# MCU.net
KiCad netlist of a schematic drawn in Altium Designer
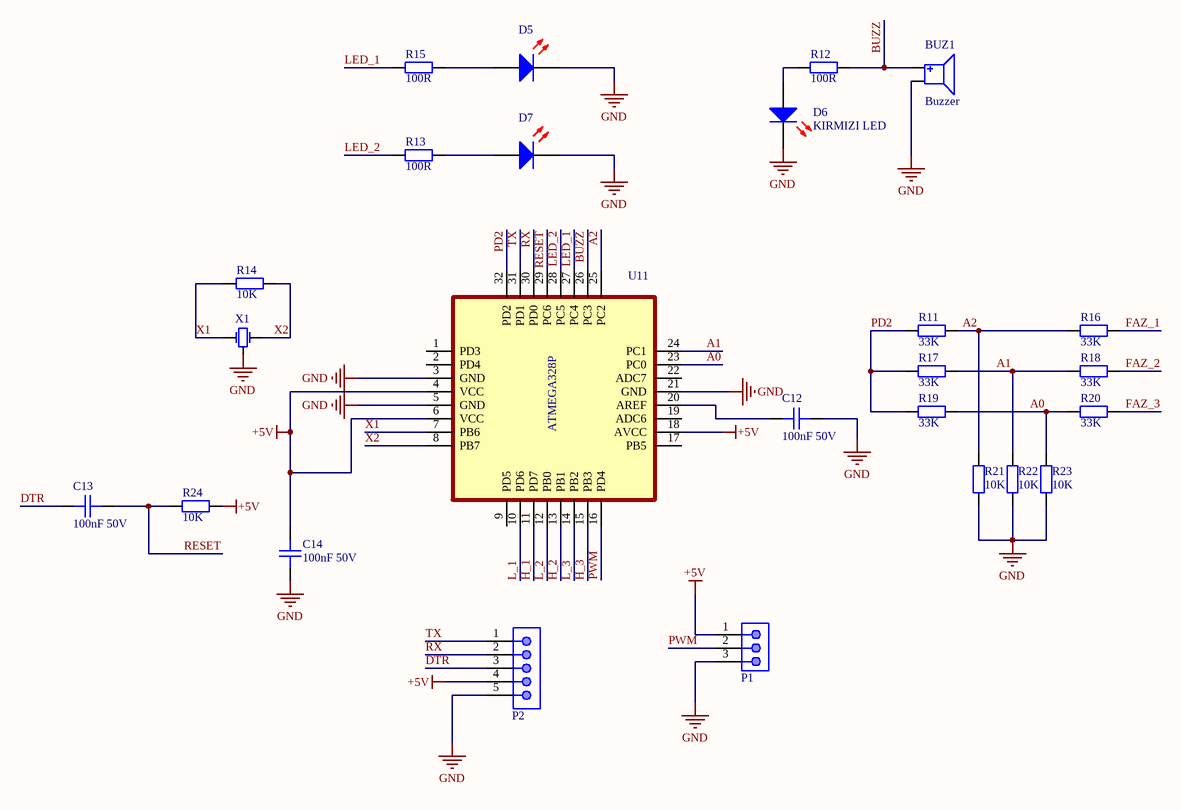
[diagram p0: MCU.SchDoc]

(export (version "E")
  (design (tool "Eeschema 10.0.6"))
  (components
    (comp (ref "BUZ1")
      (value "BUZZER MAGN 3.6V 7.5X7.5MM SMD")
      (footprint "BUZ: CMT-7525")
      (fields (field (name "DEGER") "Buzzer"))
      (libsource (lib "PROJE") (part "Buzzer(CMT-7525-80-SMT-TR)"))
    )
    (comp (ref "C12")
      (value "CAP CER 0.1UF 50V X7R 0805")
      (footprint "CAP 0805/2012")
      (description "0.1µF ±10% 50V Ceramic Capacitor X7R 0805 (2012 Metric)")
      (fields (field (name "DEGER") "100nF 50V"))
      (libsource (lib "PROJE") (part "100nF 50V 0805"))
    )
    (comp (ref "C13")
      (value "CAP CER 0.1UF 50V X7R 0805")
      (footprint "CAP 0805/2012")
      (description "0.1µF ±10% 50V Ceramic Capacitor X7R 0805 (2012 Metric)")
      (fields (field (name "DEGER") "100nF 50V"))
      (libsource (lib "PROJE") (part "100nF 50V 0805"))
    )
    (comp (ref "C14")
      (value "CAP CER 0.1UF 50V X7R 0805")
      (footprint "CAP 0805/2012")
      (description "0.1µF ±10% 50V Ceramic Capacitor X7R 0805 (2012 Metric)")
      (fields (field (name "DEGER") "100nF 50V"))
      (libsource (lib "PROJE") (part "100nF 50V 0805"))
    )
    (comp (ref "D5")
      (value "Red 645nm LED Indication - Discrete 1.8V 0805")
      (footprint "SMD: LED 0805/2012 RED")
      (description "LED RED DIFFUSED 0805 SMD")
      (libsource (lib "PROJE") (part "LED_Kırmızı"))
    )
    (comp (ref "D6")
      (value "Red 645nm LED Indication - Discrete 1.8V 0805")
      (footprint "SMD: LED 0805/2012 RED")
      (description "LED RED DIFFUSED 0805 SMD")
      (fields (field (name "DEGER") "KIRMIZI LED"))
      (libsource (lib "PROJE") (part "LED_Kırmızı"))
    )
    (comp (ref "D7")
      (value "Red 645nm LED Indication - Discrete 1.8V 0805")
      (footprint "SMD: LED 0805/2012 RED")
      (description "LED RED DIFFUSED 0805 SMD")
      (libsource (lib "PROJE") (part "LED_Kırmızı"))
    )
    (comp (ref "P1")
      (value "WR-PHD 2.54 mm Angled Socket Header")
      (footprint "PWM_CONN")
      (libsource (lib "PROJE") (part "HDR(1X3)"))
    )
    (comp (ref "P2")
      (value "WR-PHD 2.54 mm Angled Socket Header")
      (footprint "TTL_CONN_5")
      (libsource (lib "PROJE") (part "HDR(1X5)"))
    )
    (comp (ref "R11")
      (value "RES SMD 33K OHM 1% 1/8W 0805")
      (footprint "RES_0805")
      (description "33 kOhms ±1% 0.125W, 1/8W Chip Resistor 0805 (2012 Metric) Moisture Resistant Thick Film")
      (fields (field (name "DEGER") "33K"))
      (libsource (lib "PROJE") (part "33K 0805"))
    )
    (comp (ref "R12")
      (value "RES SMD 100 OHM 1% 1/8W 0805")
      (footprint "RES_0805")
      (description "100 Ohms ±1% 0.125W, 1/8W Chip Resistor 0805 (2012 Metric) Moisture Resistant Thick Film")
      (fields (field (name "DEGER") "100R"))
      (libsource (lib "PROJE") (part "100R 0805"))
    )
    (comp (ref "R13")
      (value "RES SMD 100 OHM 1% 1/8W 0805")
      (footprint "RES_0805")
      (description "100 Ohms ±1% 0.125W, 1/8W Chip Resistor 0805 (2012 Metric) Moisture Resistant Thick Film")
      (fields (field (name "DEGER") "100R"))
      (libsource (lib "PROJE") (part "100R 0805"))
    )
    (comp (ref "R14")
      (value "RES SMD 10K OHM 1% 1/8W 0805")
      (footprint "RES_0805")
      (description "10 kOhms ±1% 0.125W, 1/8W Chip Resistor 0805 (2012 Metric) Moisture Resistant Thick Film")
      (fields (field (name "DEGER") "10K"))
      (libsource (lib "PROJE") (part "10K 0805"))
    )
    (comp (ref "R15")
      (value "RES SMD 100 OHM 1% 1/8W 0805")
      (footprint "RES_0805")
      (description "100 Ohms ±1% 0.125W, 1/8W Chip Resistor 0805 (2012 Metric) Moisture Resistant Thick Film")
      (fields (field (name "DEGER") "100R"))
      (libsource (lib "PROJE") (part "100R 0805"))
    )
    (comp (ref "R16")
      (value "RES SMD 33K OHM 1% 1/8W 0805")
      (footprint "RES_0805")
      (description "33 kOhms ±1% 0.125W, 1/8W Chip Resistor 0805 (2012 Metric) Moisture Resistant Thick Film")
      (fields (field (name "DEGER") "33K"))
      (libsource (lib "PROJE") (part "33K 0805"))
    )
    (comp (ref "R17")
      (value "RES SMD 33K OHM 1% 1/8W 0805")
      (footprint "RES_0805")
      (description "33 kOhms ±1% 0.125W, 1/8W Chip Resistor 0805 (2012 Metric) Moisture Resistant Thick Film")
      (fields (field (name "DEGER") "33K"))
      (libsource (lib "PROJE") (part "33K 0805"))
    )
    (comp (ref "R18")
      (value "RES SMD 33K OHM 1% 1/8W 0805")
      (footprint "RES_0805")
      (description "33 kOhms ±1% 0.125W, 1/8W Chip Resistor 0805 (2012 Metric) Moisture Resistant Thick Film")
      (fields (field (name "DEGER") "33K"))
      (libsource (lib "PROJE") (part "33K 0805"))
    )
    (comp (ref "R19")
      (value "RES SMD 33K OHM 1% 1/8W 0805")
      (footprint "RES_0805")
      (description "33 kOhms ±1% 0.125W, 1/8W Chip Resistor 0805 (2012 Metric) Moisture Resistant Thick Film")
      (fields (field (name "DEGER") "33K"))
      (libsource (lib "PROJE") (part "33K 0805"))
    )
    (comp (ref "R20")
      (value "RES SMD 33K OHM 1% 1/8W 0805")
      (footprint "RES_0805")
      (description "33 kOhms ±1% 0.125W, 1/8W Chip Resistor 0805 (2012 Metric) Moisture Resistant Thick Film")
      (fields (field (name "DEGER") "33K"))
      (libsource (lib "PROJE") (part "33K 0805"))
    )
    (comp (ref "R21")
      (value "RES SMD 10K OHM 1% 1/8W 0805")
      (footprint "RES_0805")
      (description "10 kOhms ±1% 0.125W, 1/8W Chip Resistor 0805 (2012 Metric) Moisture Resistant Thick Film")
      (fields (field (name "DEGER") "10K"))
      (libsource (lib "") (part "10K 0805_1"))
    )
    (comp (ref "R22")
      (value "RES SMD 10K OHM 1% 1/8W 0805")
      (footprint "RES_0805")
      (description "10 kOhms ±1% 0.125W, 1/8W Chip Resistor 0805 (2012 Metric) Moisture Resistant Thick Film")
      (fields (field (name "DEGER") "10K"))
      (libsource (lib "") (part "10K 0805_1"))
    )
    (comp (ref "R23")
      (value "RES SMD 10K OHM 1% 1/8W 0805")
      (footprint "RES_0805")
      (description "10 kOhms ±1% 0.125W, 1/8W Chip Resistor 0805 (2012 Metric) Moisture Resistant Thick Film")
      (fields (field (name "DEGER") "10K"))
      (libsource (lib "") (part "10K 0805_1"))
    )
    (comp (ref "R24")
      (value "RES SMD 10K OHM 1% 1/8W 0805")
      (footprint "RES_0805")
      (description "10 kOhms ±1% 0.125W, 1/8W Chip Resistor 0805 (2012 Metric) Moisture Resistant Thick Film")
      (fields (field (name "DEGER") "10K"))
      (libsource (lib "PROJE") (part "10K 0805"))
    )
    (comp (ref "U11")
      (value "IC MCU 8BIT 32KB FLASH 32TQFP")
      (footprint "TQFP32")
      (description "AVR AVR® ATmega Microcontroller IC 8-Bit 20MHz 32KB (16K x 16) FLASH 32-TQFP (7x7)")
      (fields (field (name "DEGER") "ATMEGA328P"))
      (libsource (lib "PROJE") (part "ATMEGA328P"))
    )
    (comp (ref "X1")
      (value "CERAMIC RES 16.0000MHZ 15PF SMD")
      (footprint "CRYSTAL_16MHZ(CTSE16)")
      (description "16MHz Ceramic Resonator Built in Capacitor 15pF ±0.3%  -20°C ~ 80°C Surface Mount")
      (libsource (lib "PROJE") (part "CRYSTAL 16.0000MHZ(CSTCE16M0V53-R0)"))
    )
  )
  (nets
    (net (code "1") (name "+5V") (class "Default")
      (node (ref "C14") (pin "1") (pinfunction "1_1") (pintype "passive"))
      (node (ref "P1") (pin "1") (pinfunction "1_1") (pintype "passive"))
      (node (ref "P2") (pin "4") (pinfunction "4_4") (pintype "passive"))
      (node (ref "R24") (pin "2") (pinfunction "2_2") (pintype "passive"))
      (node (ref "U11") (pin "18") (pinfunction "AVCC_18") (pintype "passive"))
      (node (ref "U11") (pin "4") (pinfunction "VCC_4") (pintype "passive"))
      (node (ref "U11") (pin "6") (pinfunction "VCC_6") (pintype "passive"))
    )
    (net (code "2") (name "/A0") (class "Default")
      (node (ref "R19") (pin "2") (pinfunction "2_2") (pintype "passive"))
      (node (ref "R20") (pin "1") (pinfunction "1_1") (pintype "passive"))
      (node (ref "R23") (pin "2") (pinfunction "2_2") (pintype "passive"))
      (node (ref "U11") (pin "23") (pinfunction "PC0_23") (pintype "passive"))
    )
    (net (code "3") (name "/A1") (class "Default")
      (node (ref "R17") (pin "2") (pinfunction "2_2") (pintype "passive"))
      (node (ref "R18") (pin "1") (pinfunction "1_1") (pintype "passive"))
      (node (ref "R22") (pin "2") (pinfunction "2_2") (pintype "passive"))
      (node (ref "U11") (pin "24") (pinfunction "PC1_24") (pintype "passive"))
    )
    (net (code "4") (name "/A2") (class "Default")
      (node (ref "R11") (pin "2") (pinfunction "2_2") (pintype "passive"))
      (node (ref "R16") (pin "1") (pinfunction "1_1") (pintype "passive"))
      (node (ref "R21") (pin "2") (pinfunction "2_2") (pintype "passive"))
      (node (ref "U11") (pin "25") (pinfunction "PC2_25") (pintype "passive"))
    )
    (net (code "5") (name "/BUZZ") (class "Default")
      (node (ref "BUZ1") (pin "1") (pinfunction "Positive_1") (pintype "passive"))
      (node (ref "R12") (pin "2") (pinfunction "2_2") (pintype "passive"))
      (node (ref "U11") (pin "26") (pinfunction "PC3_26") (pintype "passive"))
    )
    (net (code "6") (name "/DTR") (class "Default")
      (node (ref "C13") (pin "1") (pinfunction "1_1") (pintype "passive"))
      (node (ref "P2") (pin "3") (pinfunction "3_3") (pintype "passive"))
    )
    (net (code "7") (name "/FAZ_1") (class "Default")
      (node (ref "R16") (pin "2") (pinfunction "2_2") (pintype "passive"))
    )
    (net (code "8") (name "/FAZ_2") (class "Default")
      (node (ref "R18") (pin "2") (pinfunction "2_2") (pintype "passive"))
    )
    (net (code "9") (name "/FAZ_3") (class "Default")
      (node (ref "R20") (pin "2") (pinfunction "2_2") (pintype "passive"))
    )
    (net (code "10") (name "/H_1") (class "Default")
      (node (ref "U11") (pin "11") (pinfunction "PD7_11") (pintype "passive"))
    )
    (net (code "11") (name "/H_2") (class "Default")
      (node (ref "U11") (pin "13") (pinfunction "PB1_13") (pintype "passive"))
    )
    (net (code "12") (name "/H_3") (class "Default")
      (node (ref "U11") (pin "15") (pinfunction "PB3_15") (pintype "passive"))
    )
    (net (code "13") (name "/LED_1") (class "Default")
      (node (ref "R15") (pin "1") (pinfunction "1_1") (pintype "passive"))
      (node (ref "U11") (pin "27") (pinfunction "PC4_27") (pintype "passive"))
    )
    (net (code "14") (name "/LED_2") (class "Default")
      (node (ref "R13") (pin "1") (pinfunction "1_1") (pintype "passive"))
      (node (ref "U11") (pin "28") (pinfunction "PC5_28") (pintype "passive"))
    )
    (net (code "15") (name "/L_1") (class "Default")
      (node (ref "U11") (pin "10") (pinfunction "PD6_10") (pintype "passive"))
    )
    (net (code "16") (name "/L_2") (class "Default")
      (node (ref "U11") (pin "12") (pinfunction "PB0_12") (pintype "passive"))
    )
    (net (code "17") (name "/L_3") (class "Default")
      (node (ref "U11") (pin "14") (pinfunction "PB2_14") (pintype "passive"))
    )
    (net (code "18") (name "/PD2") (class "Default")
      (node (ref "R11") (pin "1") (pinfunction "1_1") (pintype "passive"))
      (node (ref "R17") (pin "1") (pinfunction "1_1") (pintype "passive"))
      (node (ref "R19") (pin "1") (pinfunction "1_1") (pintype "passive"))
      (node (ref "U11") (pin "32") (pinfunction "PD2_32") (pintype "passive"))
    )
    (net (code "19") (name "/PWM") (class "Default")
      (node (ref "P1") (pin "2") (pinfunction "2_2") (pintype "passive"))
      (node (ref "U11") (pin "16") (pinfunction "PD4_16") (pintype "passive"))
    )
    (net (code "20") (name "/RESET") (class "Default")
      (node (ref "C13") (pin "2") (pinfunction "2_2") (pintype "passive"))
      (node (ref "R24") (pin "1") (pinfunction "1_1") (pintype "passive"))
      (node (ref "U11") (pin "29") (pinfunction "PC6_29") (pintype "passive"))
    )
    (net (code "21") (name "/RX") (class "Default")
      (node (ref "P2") (pin "2") (pinfunction "2_2") (pintype "passive"))
      (node (ref "U11") (pin "30") (pinfunction "PD0_30") (pintype "passive"))
    )
    (net (code "22") (name "/TX") (class "Default")
      (node (ref "P2") (pin "1") (pinfunction "1_1") (pintype "passive"))
      (node (ref "U11") (pin "31") (pinfunction "PD1_31") (pintype "passive"))
    )
    (net (code "23") (name "/X1") (class "Default")
      (node (ref "R14") (pin "1") (pinfunction "1_1") (pintype "passive"))
      (node (ref "U11") (pin "7") (pinfunction "PB6_7") (pintype "passive"))
      (node (ref "X1") (pin "1") (pinfunction "OSC1_1") (pintype "passive"))
    )
    (net (code "24") (name "/X2") (class "Default")
      (node (ref "R14") (pin "2") (pinfunction "2_2") (pintype "passive"))
      (node (ref "U11") (pin "8") (pinfunction "PB7_8") (pintype "passive"))
      (node (ref "X1") (pin "3") (pinfunction "OSC2_3") (pintype "passive"))
    )
    (net (code "25") (name "GND") (class "Default")
      (node (ref "BUZ1") (pin "2") (pinfunction "Negative_2") (pintype "passive"))
      (node (ref "C12") (pin "2") (pinfunction "2_2") (pintype "passive"))
      (node (ref "C14") (pin "2") (pinfunction "2_2") (pintype "passive"))
      (node (ref "D5") (pin "2") (pinfunction "K_2") (pintype "passive"))
      (node (ref "D6") (pin "2") (pinfunction "K_2") (pintype "passive"))
      (node (ref "D7") (pin "2") (pinfunction "K_2") (pintype "passive"))
      (node (ref "P1") (pin "3") (pinfunction "3_3") (pintype "passive"))
      (node (ref "P2") (pin "5") (pinfunction "5_5") (pintype "passive"))
      (node (ref "R21") (pin "1") (pinfunction "1_1") (pintype "passive"))
      (node (ref "R22") (pin "1") (pinfunction "1_1") (pintype "passive"))
      (node (ref "R23") (pin "1") (pinfunction "1_1") (pintype "passive"))
      (node (ref "U11") (pin "21") (pinfunction "GND_21") (pintype "passive"))
      (node (ref "U11") (pin "3") (pinfunction "GND_3") (pintype "passive"))
      (node (ref "U11") (pin "5") (pinfunction "GND_5") (pintype "passive"))
      (node (ref "X1") (pin "2") (pinfunction "GND_2") (pintype "passive"))
    )
    (net (code "26") (name "Net-(D5-A)") (class "Default")
      (node (ref "D5") (pin "1") (pinfunction "A_1") (pintype "passive"))
      (node (ref "R15") (pin "2") (pinfunction "2_2") (pintype "passive"))
    )
    (net (code "27") (name "Net-(D6-A)") (class "Default")
      (node (ref "D6") (pin "1") (pinfunction "A_1") (pintype "passive"))
      (node (ref "R12") (pin "1") (pinfunction "1_1") (pintype "passive"))
    )
    (net (code "28") (name "Net-(D7-A)") (class "Default")
      (node (ref "D7") (pin "1") (pinfunction "A_1") (pintype "passive"))
      (node (ref "R13") (pin "2") (pinfunction "2_2") (pintype "passive"))
    )
    (net (code "29") (name "Net-(U11-AREF)") (class "Default")
      (node (ref "C12") (pin "1") (pinfunction "1_1") (pintype "passive"))
      (node (ref "U11") (pin "20") (pinfunction "AREF_20") (pintype "passive"))
    )
    (net (code "30") (name "unconnected-(U11-ADC6-Pad19)") (class "Default")
      (node (ref "U11") (pin "19") (pinfunction "ADC6_19") (pintype "passive"))
    )
    (net (code "31") (name "unconnected-(U11-ADC7-Pad22)") (class "Default")
      (node (ref "U11") (pin "22") (pinfunction "ADC7_22") (pintype "passive"))
    )
    (net (code "32") (name "unconnected-(U11-PB5-Pad17)") (class "Default")
      (node (ref "U11") (pin "17") (pinfunction "PB5_17") (pintype "passive"))
    )
    (net (code "33") (name "unconnected-(U11-PD3-Pad1)") (class "Default")
      (node (ref "U11") (pin "1") (pinfunction "PD3_1") (pintype "passive"))
    )
    (net (code "34") (name "unconnected-(U11-PD4-Pad2)") (class "Default")
      (node (ref "U11") (pin "2") (pinfunction "PD4_2") (pintype "passive"))
    )
    (net (code "35") (name "unconnected-(U11-PD5-Pad9)") (class "Default")
      (node (ref "U11") (pin "9") (pinfunction "PD5_9") (pintype "passive"))
    )
  )
)
